# ESP32.net
KiCad netlist of a schematic drawn in Altium Designer
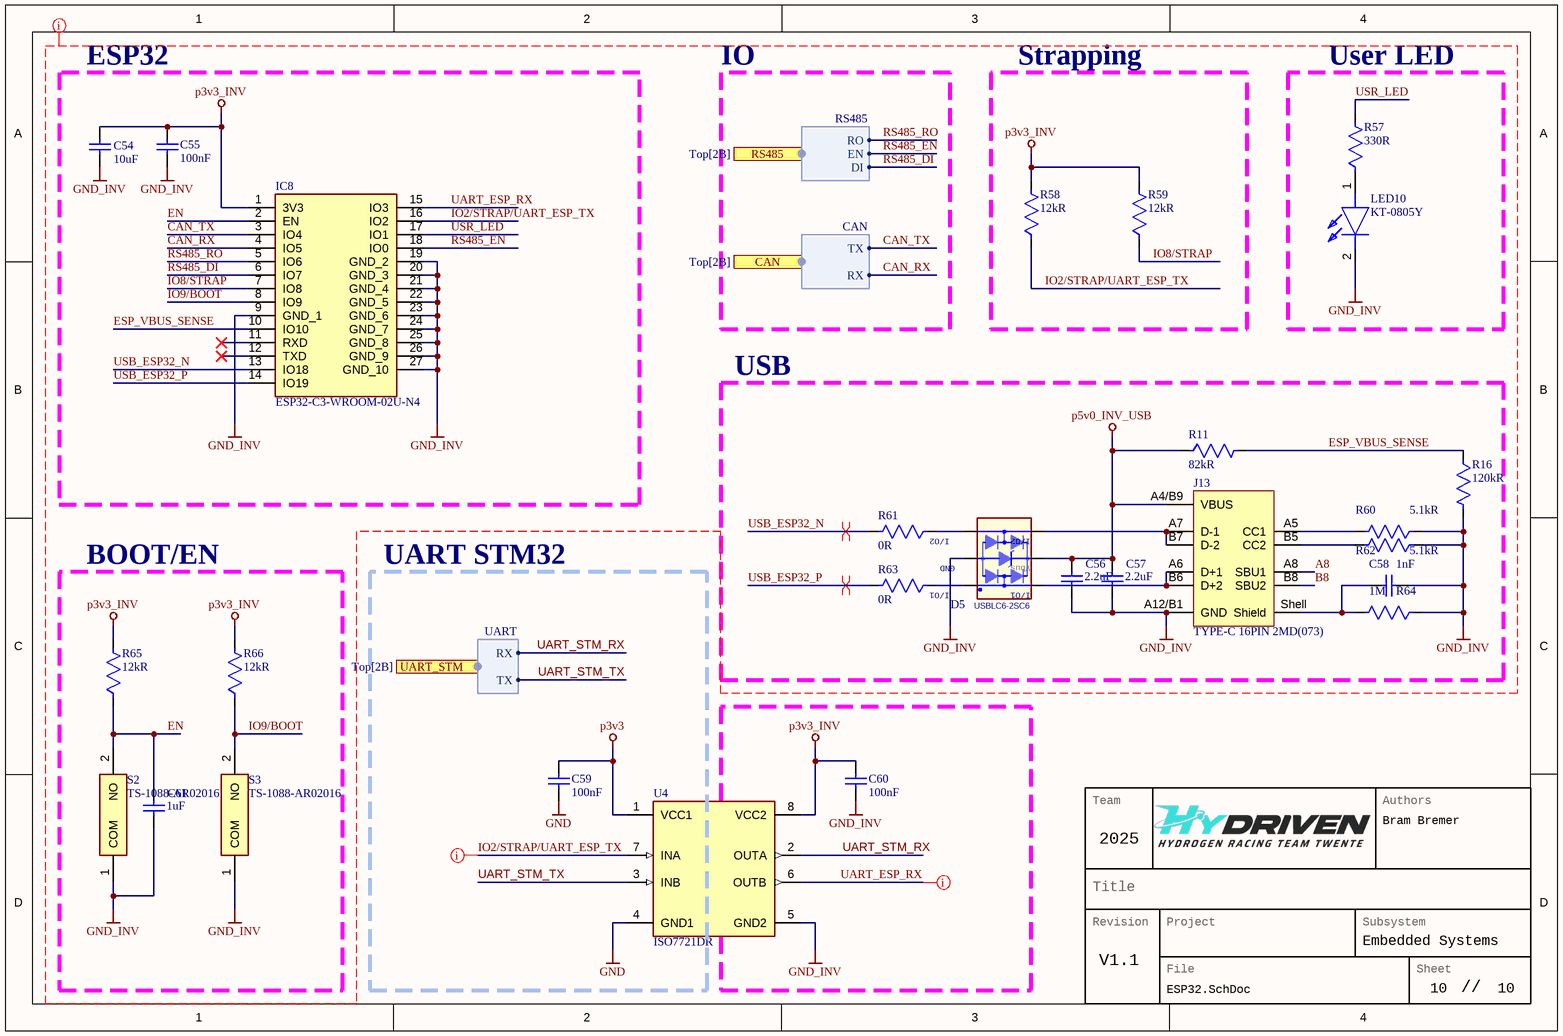
[diagram p0: ESP32.SchDoc]

(export (version "E")
  (design (tool "Eeschema 10.0.6"))
  (components
    (comp (ref "C54")
      (value "10uF")
      (footprint "WCAP-CSGP_1206_L3.2W1.6H1.15")
      (description "GTT Standard 1206 non-polarized capacitor")
      (fields (field (name "JLCPCB PART #") "C13585") (field (name "Comment") "CAP 1206 10uF X7R"))
      (libsource (lib "Green Team Twente") (part "CAP_NONPOL_GENERIC"))
    )
    (comp (ref "C55")
      (value "100nF")
      (footprint "WCAP-CSGP_0402_L1W0.5H0.5")
      (description "GTT Standard 0402 non-polarized capacitor")
      (fields (field (name "JLCPCB PART #") "C1525") (field (name "Comment") "CAP 0402 100nF X7R"))
      (libsource (lib "Green Team Twente") (part "CAP_NONPOL_GENERIC"))
    )
    (comp (ref "C56")
      (value "2.2uF")
      (footprint "WCAP-CSGP_0603_L1.6W0.8H0.8_Reflow")
      (description "GTT Standard 0603 non-polarized capacitor")
      (fields (field (name "JLCPCB PART #") "C23630") (field (name "Comment") "CAP 0603 2.2uF X7R"))
      (libsource (lib "Green Team Twente") (part "CAP_NONPOL_GENERIC"))
    )
    (comp (ref "C57")
      (value "2.2uF")
      (footprint "WCAP-CSGP_0603_L1.6W0.8H0.8_Reflow")
      (description "GTT Standard 0603 non-polarized capacitor")
      (fields (field (name "JLCPCB PART #") "C23630") (field (name "Comment") "CAP 0603 2.2uF X7R"))
      (libsource (lib "Green Team Twente") (part "CAP_NONPOL_GENERIC"))
    )
    (comp (ref "C58")
      (value "1nF")
      (footprint "WCAP-CSGP_1206_L3.2W1.6H1.15")
      (description "GTT Standard 1206 non-polarized capacitor")
      (fields (field (name "JLCPCB PART #") "C9196") (field (name "Comment") "CAP 1206 1nF X7R"))
      (libsource (lib "Green Team Twente") (part "CAP_NONPOL_GENERIC"))
    )
    (comp (ref "C59")
      (value "100nF")
      (footprint "WCAP-CSGP_0402_L1W0.5H0.5")
      (description "GTT Standard 0402 non-polarized capacitor")
      (fields (field (name "JLCPCB PART #") "C1525") (field (name "Comment") "CAP 0402 100nF X7R"))
      (libsource (lib "Green Team Twente") (part "CAP_NONPOL_GENERIC"))
    )
    (comp (ref "C60")
      (value "100nF")
      (footprint "WCAP-CSGP_0402_L1W0.5H0.5")
      (description "GTT Standard 0402 non-polarized capacitor")
      (fields (field (name "JLCPCB PART #") "C1525") (field (name "Comment") "CAP 0402 100nF X7R"))
      (libsource (lib "Green Team Twente") (part "CAP_NONPOL_GENERIC"))
    )
    (comp (ref "C61")
      (value "1uF")
      (footprint "WCAP-CSGP_0402_L1W0.5H0.5")
      (description "GTT Standard 0402 non-polarized capacitor")
      (fields (field (name "JLCPCB PART #") "C52923") (field (name "Comment") "CAP 0402 1uF X7R"))
      (libsource (lib "Green Team Twente") (part "CAP_NONPOL_GENERIC"))
    )
    (comp (ref "D5")
      (value "USBLC6-2SC6")
      (footprint "ST_SOT23-6L")
      (libsource (lib "Green Team Twente") (part "USBLC6-2SC6"))
    )
    (comp (ref "IC8")
      (value "ESP32-C3-WROOM-02U-N4")
      (footprint "ESP32C3WROOM02UN4")
      (description "Integrated Circuit")
      (fields (field (name "MOUSER PART NUMBER") "356-ESP32C3WROM02UN4"))
      (libsource (lib "FlexBMS_lib") (part "ESP32-C3-WROOM-02U-N4"))
    )
    (comp (ref "J13")
      (value "TYPE-C 16PIN 2MD(073)")
      (footprint "629722000214")
      (description "WR-USB 2.0 Type C, Receptacle, Horizontal, SMT")
      (fields
        (field (name "MANUFACTURER") "Wurth Elektronik")
        (field (name "MANUFACTURER PART NUMBER") "629722000214")
      )
      (libsource (lib "Green Team Twente") (part "USB-C"))
    )
    (comp (ref "LED10")
      (value "KT-0805Y")
      (footprint "KT0805G")
      (description "LED")
      (fields (field (name "MANUFACTURER_PART_NUMBER") "KT-0805G") (field (name "JLCPCB PART #") "C2296"))
      (libsource (lib "FlexBMS_lib") (part "KT-0805G"))
    )
    (comp (ref "R11")
      (value "82kR")
      (footprint "RES_SM0603_YAGEORC_N")
      (description "GTT Standard 0603 Resistor")
      (fields (field (name "POWER") "62.5mW") (field (name "TOLERANCE") "1%"))
      (libsource (lib "Green Team Twente") (part "RES_GENERIC"))
    )
    (comp (ref "R16")
      (value "120kR")
      (footprint "RES_SM0603_YAGEORC_N")
      (description "GTT Standard 0603 Resistor")
      (fields (field (name "POWER") "62.5mW") (field (name "TOLERANCE") "1%"))
      (libsource (lib "Green Team Twente") (part "RES_GENERIC"))
    )
    (comp (ref "R57")
      (value "330R")
      (footprint "RES_SM0603_YAGEORC_N")
      (description "GTT Standard 0603 Resistor")
      (fields (field (name "POWER") "62.5mW") (field (name "TOLERANCE") "1%"))
      (libsource (lib "Green Team Twente") (part "RES_GENERIC"))
    )
    (comp (ref "R58")
      (value "12kR")
      (footprint "FP0402")
      (description "GTT Standard 0402 Resistor")
      (fields (field (name "TOLERANCE") "1%") (field (name "POWER") "62.5mW"))
      (libsource (lib "Green Team Twente") (part "RES_GENERIC"))
    )
    (comp (ref "R59")
      (value "12kR")
      (footprint "FP0402")
      (description "GTT Standard 0402 Resistor")
      (fields (field (name "TOLERANCE") "1%") (field (name "POWER") "62.5mW"))
      (libsource (lib "Green Team Twente") (part "RES_GENERIC"))
    )
    (comp (ref "R60")
      (value "5.1kR")
      (footprint "FP0402")
      (description "GTT Standard 0402 Resistor")
      (fields (field (name "TOLERANCE") "1%") (field (name "POWER") "62.5mW"))
      (libsource (lib "Green Team Twente") (part "RES_GENERIC"))
    )
    (comp (ref "R61")
      (value "0R")
      (footprint "FP0402")
      (description "GTT Standard 0402 Resistor")
      (fields (field (name "TOLERANCE") "1%") (field (name "POWER") "62.5mW"))
      (libsource (lib "Green Team Twente") (part "RES_GENERIC"))
    )
    (comp (ref "R62")
      (value "5.1kR")
      (footprint "FP0402")
      (description "GTT Standard 0402 Resistor")
      (fields (field (name "TOLERANCE") "1%") (field (name "POWER") "62.5mW"))
      (libsource (lib "Green Team Twente") (part "RES_GENERIC"))
    )
    (comp (ref "R63")
      (value "0R")
      (footprint "FP0402")
      (description "GTT Standard 0402 Resistor")
      (fields (field (name "TOLERANCE") "1%") (field (name "POWER") "62.5mW"))
      (libsource (lib "Green Team Twente") (part "RES_GENERIC"))
    )
    (comp (ref "R64")
      (value "1M")
      (footprint "RES_SM1206_YAGEORC_N")
      (description "GTT Standard 1206 Resistor")
      (fields (field (name "TOLERANCE") "1%") (field (name "POWER") "62.5mW"))
      (libsource (lib "Green Team Twente") (part "RES_GENERIC"))
    )
    (comp (ref "R65")
      (value "12kR")
      (footprint "FP0402")
      (description "GTT Standard 0402 Resistor")
      (fields (field (name "TOLERANCE") "1%") (field (name "POWER") "62.5mW"))
      (libsource (lib "Green Team Twente") (part "RES_GENERIC"))
    )
    (comp (ref "R66")
      (value "12kR")
      (footprint "FP0402")
      (description "GTT Standard 0402 Resistor")
      (fields (field (name "TOLERANCE") "1%") (field (name "POWER") "62.5mW"))
      (libsource (lib "Green Team Twente") (part "RES_GENERIC"))
    )
    (comp (ref "S2")
      (value "TS-1088-AR02016")
      (footprint "TS1088AR02016")
      (description "Switch")
      (libsource (lib "FlexBMS_lib") (part "TS-1088-AR02016"))
    )
    (comp (ref "S3")
      (value "TS-1088-AR02016")
      (footprint "TS1088AR02016")
      (description "Switch")
      (libsource (lib "FlexBMS_lib") (part "TS-1088-AR02016"))
    )
    (comp (ref "U4")
      (value "ISO7721DR")
      (footprint "FP-D0008B-MFG")
      (description "DGTL ISO 3KV GEN PRP 8SOIC")
      (libsource (lib "Altium Content Vault") (part "d04888473b947ce0c6c1d96650364e2"))
    )
  )
  (nets
    (net (code "4") (name "/A8") (class "Default")
      (node (ref "J13") (pin "A8") (pinfunction "SBU1_A8") (pintype "passive"))
    )
    (net (code "5") (name "/B8") (class "Default")
      (node (ref "J13") (pin "B8") (pinfunction "SBU2_B8") (pintype "passive"))
    )
    (net (code "6") (name "/CAN_RX") (class "Default")
      (node (ref "IC8") (pin "4") (pinfunction "IO5_4") (pintype "passive"))
    )
    (net (code "7") (name "/CAN_TX") (class "Default")
      (node (ref "IC8") (pin "3") (pinfunction "IO4_3") (pintype "passive"))
    )
    (net (code "8") (name "/EN") (class "Default")
      (node (ref "C61") (pin "2") (pinfunction "2_2") (pintype "passive"))
      (node (ref "IC8") (pin "2") (pinfunction "EN_2") (pintype "passive"))
      (node (ref "R65") (pin "1") (pinfunction "1_1") (pintype "passive"))
      (node (ref "S2") (pin "2") (pinfunction "NO_2") (pintype "passive"))
    )
    (net (code "9") (name "/ESP_VBUS_SENSE") (class "Default")
      (node (ref "IC8") (pin "10") (pinfunction "IO10_10") (pintype "passive"))
      (node (ref "R11") (pin "2") (pinfunction "2_2") (pintype "passive"))
      (node (ref "R16") (pin "1") (pinfunction "1_1") (pintype "passive"))
    )
    (net (code "10") (name "/IO2{slash}STRAP{slash}UART_ESP_TX") (class "Default")
      (node (ref "IC8") (pin "16") (pinfunction "IO2_16") (pintype "passive"))
      (node (ref "R58") (pin "1") (pinfunction "1_1") (pintype "passive"))
      (node (ref "U4") (pin "7") (pinfunction "INA_7") (pintype "input"))
    )
    (net (code "11") (name "/IO8{slash}STRAP") (class "Default")
      (node (ref "IC8") (pin "7") (pinfunction "IO8_7") (pintype "passive"))
      (node (ref "R59") (pin "1") (pinfunction "1_1") (pintype "passive"))
    )
    (net (code "12") (name "/IO9{slash}BOOT") (class "Default")
      (node (ref "IC8") (pin "8") (pinfunction "IO9_8") (pintype "passive"))
      (node (ref "R66") (pin "1") (pinfunction "1_1") (pintype "passive"))
      (node (ref "S3") (pin "2") (pinfunction "NO_2") (pintype "passive"))
    )
    (net (code "13") (name "/RS485_DI") (class "Default")
      (node (ref "IC8") (pin "6") (pinfunction "IO7_6") (pintype "passive"))
    )
    (net (code "14") (name "/RS485_EN") (class "Default")
      (node (ref "IC8") (pin "18") (pinfunction "IO0_18") (pintype "passive"))
    )
    (net (code "15") (name "/RS485_RO") (class "Default")
      (node (ref "IC8") (pin "5") (pinfunction "IO6_5") (pintype "passive"))
    )
    (net (code "16") (name "/UART_ESP_RX") (class "Default")
      (node (ref "IC8") (pin "15") (pinfunction "IO3_15") (pintype "passive"))
      (node (ref "U4") (pin "6") (pinfunction "OUTB_6") (pintype "output"))
    )
    (net (code "17") (name "/UART_STM_RX") (class "Default")
      (node (ref "U4") (pin "2") (pinfunction "OUTA_2") (pintype "output"))
    )
    (net (code "18") (name "/UART_STM_TX") (class "Default")
      (node (ref "U4") (pin "3") (pinfunction "INB_3") (pintype "input"))
    )
    (net (code "19") (name "/USB_ESP32_N") (class "Default")
      (node (ref "IC8") (pin "13") (pinfunction "IO18_13") (pintype "passive"))
      (node (ref "R61") (pin "2") (pinfunction "2_2") (pintype "passive"))
    )
    (net (code "20") (name "/USB_ESP32_P") (class "Default")
      (node (ref "IC8") (pin "14") (pinfunction "IO19_14") (pintype "passive"))
      (node (ref "R63") (pin "2") (pinfunction "2_2") (pintype "passive"))
    )
    (net (code "21") (name "/USR_LED") (class "Default")
      (node (ref "IC8") (pin "17") (pinfunction "IO1_17") (pintype "passive"))
      (node (ref "R57") (pin "2") (pinfunction "2_2") (pintype "passive"))
    )
    (net (code "25") (name "GND") (class "Default")
      (node (ref "C59") (pin "1") (pinfunction "1_1") (pintype "passive"))
      (node (ref "U4") (pin "4") (pinfunction "GND1_4") (pintype "power_in"))
    )
    (net (code "26") (name "GND_INV") (class "Default")
      (node (ref "C54") (pin "1") (pinfunction "1_1") (pintype "passive"))
      (node (ref "C55") (pin "2") (pinfunction "2_2") (pintype "passive"))
      (node (ref "C56") (pin "1") (pinfunction "1_1") (pintype "passive"))
      (node (ref "C57") (pin "1") (pinfunction "1_1") (pintype "passive"))
      (node (ref "C58") (pin "2") (pinfunction "2_2") (pintype "passive"))
      (node (ref "C60") (pin "1") (pinfunction "1_1") (pintype "passive"))
      (node (ref "C61") (pin "1") (pinfunction "1_1") (pintype "passive"))
      (node (ref "D5") (pin "2") (pinfunction "GND_2") (pintype "passive"))
      (node (ref "IC8") (pin "19") (pinfunction "GND_2_19") (pintype "passive"))
      (node (ref "IC8") (pin "20") (pinfunction "GND_3_20") (pintype "passive"))
      (node (ref "IC8") (pin "21") (pinfunction "GND_4_21") (pintype "passive"))
      (node (ref "IC8") (pin "22") (pinfunction "GND_5_22") (pintype "passive"))
      (node (ref "IC8") (pin "23") (pinfunction "GND_6_23") (pintype "passive"))
      (node (ref "IC8") (pin "24") (pinfunction "GND_7_24") (pintype "passive"))
      (node (ref "IC8") (pin "25") (pinfunction "GND_8_25") (pintype "passive"))
      (node (ref "IC8") (pin "26") (pinfunction "GND_9_26") (pintype "passive"))
      (node (ref "IC8") (pin "27") (pinfunction "GND_10_27") (pintype "passive"))
      (node (ref "IC8") (pin "9") (pinfunction "GND_1_9") (pintype "passive"))
      (node (ref "J13") (pin "A12/B1") (pinfunction "GND_A12/B1") (pintype "passive"))
      (node (ref "LED10") (pin "2") (pinfunction "K_2") (pintype "passive"))
      (node (ref "R16") (pin "2") (pinfunction "2_2") (pintype "passive"))
      (node (ref "R60") (pin "1") (pinfunction "1_1") (pintype "passive"))
      (node (ref "R62") (pin "1") (pinfunction "1_1") (pintype "passive"))
      (node (ref "R64") (pin "1") (pinfunction "1_1") (pintype "passive"))
      (node (ref "S2") (pin "1") (pinfunction "COM_1") (pintype "passive"))
      (node (ref "S3") (pin "1") (pinfunction "COM_1") (pintype "passive"))
      (node (ref "U4") (pin "5") (pinfunction "GND2_5") (pintype "power_in"))
    )
    (net (code "27") (name "Net-(D5-I{slash}O1)") (class "Default")
      (node (ref "D5") (pin "1") (pinfunction "I/O1_1") (pintype "passive"))
      (node (ref "R63") (pin "1") (pinfunction "1_1") (pintype "passive"))
    )
    (net (code "28") (name "Net-(D5-I{slash}O1+)") (class "Default")
      (node (ref "D5") (pin "6") (pinfunction "I/O1+_6") (pintype "passive"))
      (node (ref "J13") (pin "A6") (pinfunction "D+1_A6") (pintype "passive"))
      (node (ref "J13") (pin "B6") (pinfunction "D+2_B6") (pintype "passive"))
    )
    (net (code "29") (name "Net-(D5-I{slash}O2)") (class "Default")
      (node (ref "D5") (pin "3") (pinfunction "I/O2_3") (pintype "passive"))
      (node (ref "R61") (pin "1") (pinfunction "1_1") (pintype "passive"))
    )
    (net (code "30") (name "Net-(D5-I{slash}O2+)") (class "Default")
      (node (ref "D5") (pin "4") (pinfunction "I/O2+_4") (pintype "passive"))
      (node (ref "J13") (pin "A7") (pinfunction "D-1_A7") (pintype "passive"))
      (node (ref "J13") (pin "B7") (pinfunction "D-2_B7") (pintype "passive"))
    )
    (net (code "31") (name "Net-(J13-CC1)") (class "Default")
      (node (ref "J13") (pin "A5") (pinfunction "CC1_A5") (pintype "passive"))
      (node (ref "R60") (pin "2") (pinfunction "2_2") (pintype "passive"))
    )
    (net (code "32") (name "Net-(J13-CC2)") (class "Default")
      (node (ref "J13") (pin "B5") (pinfunction "CC2_B5") (pintype "passive"))
      (node (ref "R62") (pin "2") (pinfunction "2_2") (pintype "passive"))
    )
    (net (code "33") (name "Net-(J13-Shield)") (class "Default")
      (node (ref "C58") (pin "1") (pinfunction "1_1") (pintype "passive"))
      (node (ref "J13") (pin "Shell") (pinfunction "Shield_Shell") (pintype "passive"))
      (node (ref "R64") (pin "2") (pinfunction "2_2") (pintype "passive"))
    )
    (net (code "34") (name "Net-(LED10-A)") (class "Default")
      (node (ref "LED10") (pin "1") (pinfunction "A_1") (pintype "passive"))
      (node (ref "R57") (pin "1") (pinfunction "1_1") (pintype "passive"))
    )
    (net (code "35") (name "p3v3") (class "Default")
      (node (ref "C59") (pin "2") (pinfunction "2_2") (pintype "passive"))
      (node (ref "U4") (pin "1") (pinfunction "VCC1_1") (pintype "power_in"))
    )
    (net (code "36") (name "p3v3_INV") (class "Default")
      (node (ref "C54") (pin "2") (pinfunction "2_2") (pintype "passive"))
      (node (ref "C55") (pin "1") (pinfunction "1_1") (pintype "passive"))
      (node (ref "C60") (pin "2") (pinfunction "2_2") (pintype "passive"))
      (node (ref "IC8") (pin "1") (pinfunction "3V3_1") (pintype "passive"))
      (node (ref "R58") (pin "2") (pinfunction "2_2") (pintype "passive"))
      (node (ref "R59") (pin "2") (pinfunction "2_2") (pintype "passive"))
      (node (ref "R65") (pin "2") (pinfunction "2_2") (pintype "passive"))
      (node (ref "R66") (pin "2") (pinfunction "2_2") (pintype "passive"))
      (node (ref "U4") (pin "8") (pinfunction "VCC2_8") (pintype "power_in"))
    )
    (net (code "37") (name "p5v0_INV_USB") (class "Default")
      (node (ref "C56") (pin "2") (pinfunction "2_2") (pintype "passive"))
      (node (ref "C57") (pin "2") (pinfunction "2_2") (pintype "passive"))
      (node (ref "D5") (pin "5") (pinfunction "Vbus_5") (pintype "passive"))
      (node (ref "J13") (pin "A4/B9") (pinfunction "VBUS_A4/B9") (pintype "passive"))
      (node (ref "R11") (pin "1") (pinfunction "1_1") (pintype "passive"))
    )
    (net (code "38") (name "unconnected-(IC8-RXD-Pad11)") (class "Default")
      (node (ref "IC8") (pin "11") (pinfunction "RXD_11") (pintype "passive+no_connect"))
    )
    (net (code "39") (name "unconnected-(IC8-TXD-Pad12)") (class "Default")
      (node (ref "IC8") (pin "12") (pinfunction "TXD_12") (pintype "passive+no_connect"))
    )
  )
)
